# Sheet2.net
KiCad netlist of a schematic drawn in Altium Designer
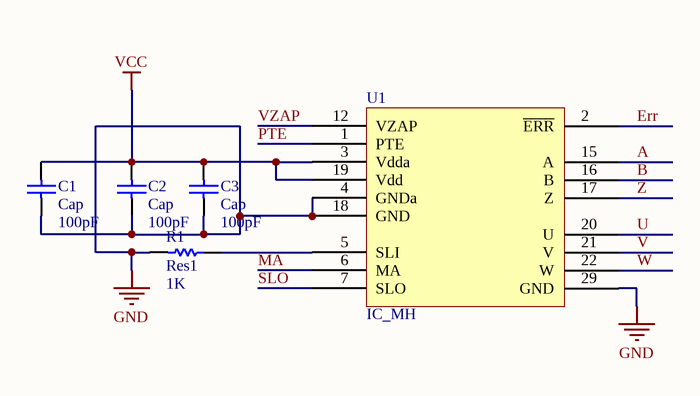
[diagram p0: Sheet2.SchDoc]

(export (version "E")
  (design (tool "Eeschema 10.0.6"))
  (components
    (comp (ref "C1")
      (value "Cap")
      (footprint "ERA-0603")
      (description "Capacitor")
      (fields (field (name "ALTIUM_VALUE") "100pF") (field (name "PUBLISHER") "Altium Limited"))
      (libsource (lib "Miscellaneous Devices") (part "Cap"))
    )
    (comp (ref "C2")
      (value "Cap")
      (footprint "ERA-0603")
      (description "Capacitor")
      (fields (field (name "ALTIUM_VALUE") "100pF") (field (name "PUBLISHER") "Altium Limited"))
      (libsource (lib "Miscellaneous Devices") (part "Cap"))
    )
    (comp (ref "C3")
      (value "Cap")
      (footprint "ERA-0603")
      (description "Capacitor")
      (fields (field (name "ALTIUM_VALUE") "100pF") (field (name "PUBLISHER") "Altium Limited"))
      (libsource (lib "Miscellaneous Devices") (part "Cap"))
    )
    (comp (ref "R1")
      (value "Res1")
      (footprint "ERA-0603")
      (description "Resistor")
      (fields (field (name "ALTIUM_VALUE") "1K") (field (name "PUBLISHER") "Altium Limited"))
      (libsource (lib "Miscellaneous Devices") (part "Res1"))
    )
    (comp (ref "U1") (value "IC_MH") (footprint "QFN28-2") (libsource (lib "Schlib1") (part "IC_MH")))
  )
  (nets
    (net (code "1") (name "/A") (class "Default")
      (node (ref "U1") (pin "15") (pinfunction "A_15") (pintype "passive"))
    )
    (net (code "2") (name "/B") (class "Default")
      (node (ref "U1") (pin "16") (pinfunction "B_16") (pintype "passive"))
    )
    (net (code "3") (name "/Err") (class "Default")
      (node (ref "U1") (pin "2") (pinfunction "~{ERR}_2") (pintype "passive"))
    )
    (net (code "4") (name "/MA") (class "Default")
      (node (ref "U1") (pin "6") (pinfunction "MA_6") (pintype "passive"))
    )
    (net (code "5") (name "/PTE") (class "Default")
      (node (ref "U1") (pin "1") (pinfunction "PTE_1") (pintype "passive"))
    )
    (net (code "6") (name "/SLO") (class "Default")
      (node (ref "U1") (pin "7") (pinfunction "SLO_7") (pintype "passive"))
    )
    (net (code "7") (name "/U") (class "Default")
      (node (ref "U1") (pin "20") (pinfunction "U_20") (pintype "passive"))
    )
    (net (code "8") (name "/V") (class "Default")
      (node (ref "U1") (pin "21") (pinfunction "V_21") (pintype "passive"))
    )
    (net (code "9") (name "/VZAP") (class "Default")
      (node (ref "U1") (pin "12") (pinfunction "VZAP_12") (pintype "passive"))
    )
    (net (code "10") (name "/W") (class "Default")
      (node (ref "U1") (pin "22") (pinfunction "W_22") (pintype "passive"))
    )
    (net (code "11") (name "/Z") (class "Default")
      (node (ref "U1") (pin "17") (pinfunction "Z_17") (pintype "passive"))
    )
    (net (code "12") (name "GND") (class "Default")
      (node (ref "C1") (pin "1") (pinfunction "1_1") (pintype "passive"))
      (node (ref "C2") (pin "1") (pinfunction "1_1") (pintype "passive"))
      (node (ref "C3") (pin "1") (pinfunction "1_1") (pintype "passive"))
      (node (ref "R1") (pin "2") (pinfunction "2_2") (pintype "passive"))
      (node (ref "U1") (pin "18") (pinfunction "GND_18") (pintype "passive"))
      (node (ref "U1") (pin "29") (pinfunction "GND_29") (pintype "power_in"))
      (node (ref "U1") (pin "4") (pinfunction "GNDa_4") (pintype "passive"))
    )
    (net (code "13") (name "Net-(U1-SLI)") (class "Default")
      (node (ref "R1") (pin "1") (pinfunction "1_1") (pintype "passive"))
      (node (ref "U1") (pin "5") (pinfunction "SLI_5") (pintype "passive"))
    )
    (net (code "14") (name "VCC") (class "Default")
      (node (ref "C1") (pin "2") (pinfunction "2_2") (pintype "passive"))
      (node (ref "C2") (pin "2") (pinfunction "2_2") (pintype "passive"))
      (node (ref "C3") (pin "2") (pinfunction "2_2") (pintype "passive"))
      (node (ref "U1") (pin "19") (pinfunction "Vdd_19") (pintype "passive"))
      (node (ref "U1") (pin "3") (pinfunction "Vdda_3") (pintype "passive"))
    )
  )
)
